# 780-00054_rev1_Pg1_SCH_Extender_for_Shor.net
KiCad netlist of a schematic drawn in Altium Designer
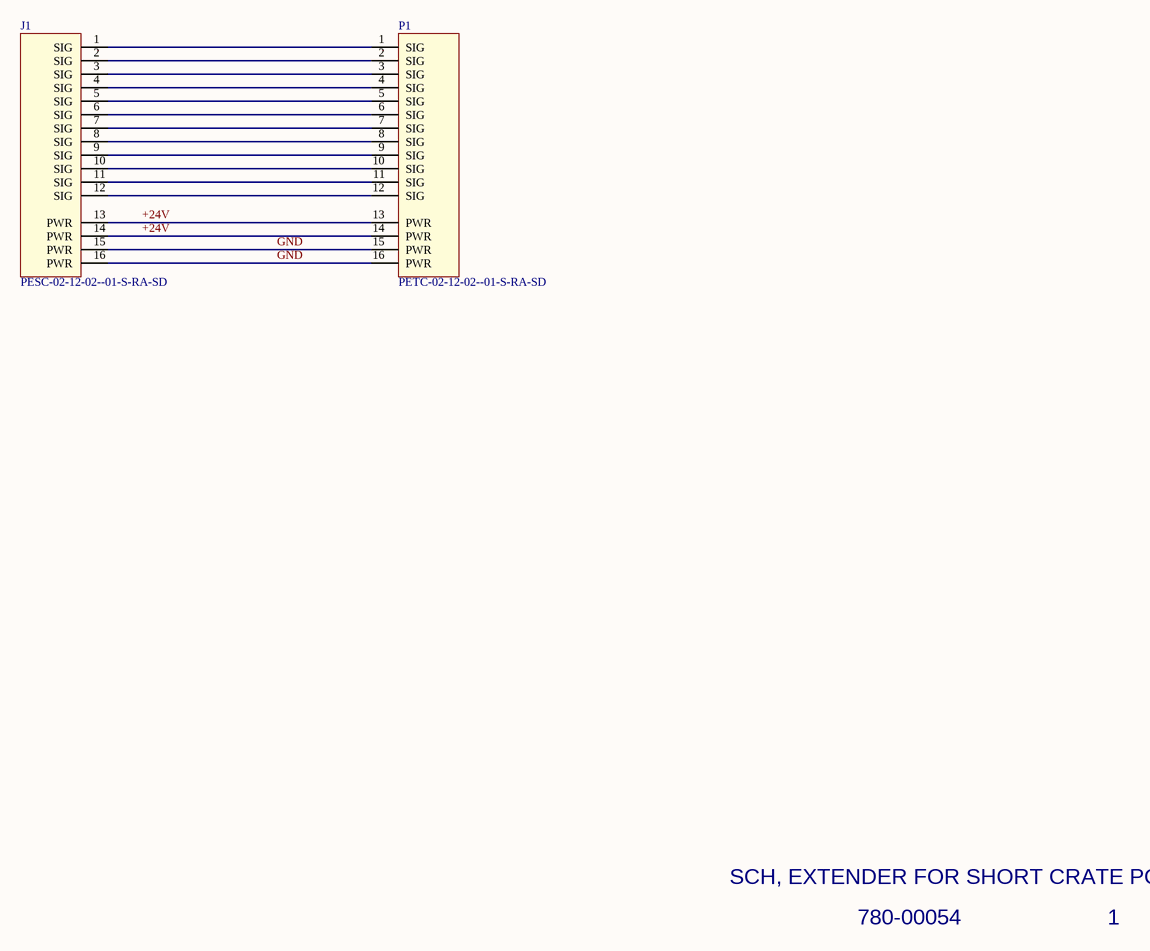
[diagram p0: 780-00054, rev1, Pg1, SCH, Extender for Short Crate PCB.SchDoc]

(export (version "E")
  (design (tool "Eeschema 10.0.6"))
  (components
    (comp (ref "J1")
      (value "PESC-02-12-02--01-S-RA-SD")
      (footprint "PESC-02-12-02-01-RA")
      (description "SAMTEC, SIGNAL(12)+PWR(4)")
      (fields (field (name "MANUFACTURER") "SAMTEC"))
      (libsource (lib "Richs Schematic Components") (part "PETC-02-12-02--01-S-RA-SD"))
    )
    (comp (ref "P1")
      (value "PETC-02-12-02--01-S-RA-SD")
      (footprint "PETC-02-12-02-01-RA")
      (description "SAMTEC, SIGNAL(12)+PWR(4)")
      (fields (field (name "MANUFACTURER") "SAMTEC"))
      (libsource (lib "") (part "PETC-02-12-02--01-S-RA-SD_1"))
    )
  )
  (nets
    (net (code "1") (name "/+24V") (class "Default")
      (node (ref "J1") (pin "13") (pinfunction "PWR_13") (pintype "passive"))
      (node (ref "J1") (pin "14") (pinfunction "PWR_14") (pintype "passive"))
      (node (ref "P1") (pin "13") (pinfunction "PWR_13") (pintype "passive"))
      (node (ref "P1") (pin "14") (pinfunction "PWR_14") (pintype "passive"))
    )
    (net (code "2") (name "/GND") (class "Default")
      (node (ref "J1") (pin "15") (pinfunction "PWR_15") (pintype "passive"))
      (node (ref "J1") (pin "16") (pinfunction "PWR_16") (pintype "passive"))
      (node (ref "P1") (pin "15") (pinfunction "PWR_15") (pintype "passive"))
      (node (ref "P1") (pin "16") (pinfunction "PWR_16") (pintype "passive"))
    )
    (net (code "3") (name "Net-(J1-SIG-Pad1)") (class "Default")
      (node (ref "J1") (pin "1") (pinfunction "SIG_1") (pintype "passive"))
      (node (ref "P1") (pin "1") (pinfunction "SIG_1") (pintype "passive"))
    )
    (net (code "4") (name "Net-(J1-SIG-Pad2)") (class "Default")
      (node (ref "J1") (pin "2") (pinfunction "SIG_2") (pintype "passive"))
      (node (ref "P1") (pin "2") (pinfunction "SIG_2") (pintype "passive"))
    )
    (net (code "5") (name "Net-(J1-SIG-Pad3)") (class "Default")
      (node (ref "J1") (pin "3") (pinfunction "SIG_3") (pintype "passive"))
      (node (ref "P1") (pin "3") (pinfunction "SIG_3") (pintype "passive"))
    )
    (net (code "6") (name "Net-(J1-SIG-Pad4)") (class "Default")
      (node (ref "J1") (pin "4") (pinfunction "SIG_4") (pintype "passive"))
      (node (ref "P1") (pin "4") (pinfunction "SIG_4") (pintype "passive"))
    )
    (net (code "7") (name "Net-(J1-SIG-Pad5)") (class "Default")
      (node (ref "J1") (pin "5") (pinfunction "SIG_5") (pintype "passive"))
      (node (ref "P1") (pin "5") (pinfunction "SIG_5") (pintype "passive"))
    )
    (net (code "8") (name "Net-(J1-SIG-Pad6)") (class "Default")
      (node (ref "J1") (pin "6") (pinfunction "SIG_6") (pintype "passive"))
      (node (ref "P1") (pin "6") (pinfunction "SIG_6") (pintype "passive"))
    )
    (net (code "9") (name "Net-(J1-SIG-Pad7)") (class "Default")
      (node (ref "J1") (pin "7") (pinfunction "SIG_7") (pintype "passive"))
      (node (ref "P1") (pin "7") (pinfunction "SIG_7") (pintype "passive"))
    )
    (net (code "10") (name "Net-(J1-SIG-Pad8)") (class "Default")
      (node (ref "J1") (pin "8") (pinfunction "SIG_8") (pintype "passive"))
      (node (ref "P1") (pin "8") (pinfunction "SIG_8") (pintype "passive"))
    )
    (net (code "11") (name "Net-(J1-SIG-Pad9)") (class "Default")
      (node (ref "J1") (pin "9") (pinfunction "SIG_9") (pintype "passive"))
      (node (ref "P1") (pin "9") (pinfunction "SIG_9") (pintype "passive"))
    )
    (net (code "12") (name "Net-(J1-SIG-Pad10)") (class "Default")
      (node (ref "J1") (pin "10") (pinfunction "SIG_10") (pintype "passive"))
      (node (ref "P1") (pin "10") (pinfunction "SIG_10") (pintype "passive"))
    )
    (net (code "13") (name "Net-(J1-SIG-Pad11)") (class "Default")
      (node (ref "J1") (pin "11") (pinfunction "SIG_11") (pintype "passive"))
      (node (ref "P1") (pin "11") (pinfunction "SIG_11") (pintype "passive"))
    )
    (net (code "14") (name "Net-(J1-SIG-Pad12)") (class "Default")
      (node (ref "J1") (pin "12") (pinfunction "SIG_12") (pintype "passive"))
      (node (ref "P1") (pin "12") (pinfunction "SIG_12") (pintype "passive"))
    )
  )
)
